# LinearSensor_inputs.net
KiCad netlist of a schematic drawn in Altium Designer
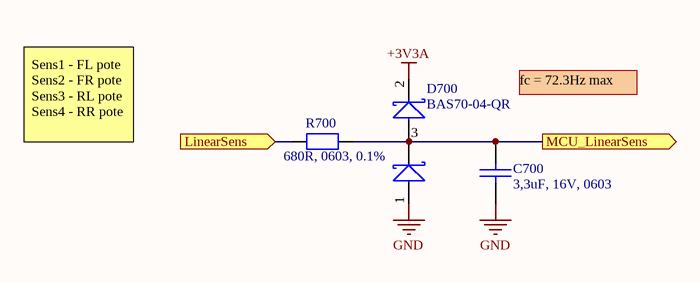
[diagram p0: LinearSensor_inputs.SchDoc]

(export (version "E")
  (design (tool "Eeschema 10.0.6"))
  (components
    (comp (ref "C700")
      (value "3,3uF, 16V, 0603")
      (footprint "CAP [0603] 1608")
      (description "Default capacitor part")
      (libsource (lib "Formula Student Team Tallinn (Estonia)") (part "Capacitor"))
    )
    (comp (ref "D700")
      (value "BAS70-04-QR")
      (footprint "SOT23-3")
      (description "Diode Small Signal Schottky 70V 70mA 3-Pin SOT-23 T/R")
      (fields (field (name "MANUFACTURER") "Nexperia"))
      (libsource (lib "Formula Student Team Tallinn (Estonia)") (part "Diode Rail-to-rail"))
    )
    (comp (ref "R700")
      (value "680R, 0603, 0.1%")
      (footprint "RES [0603] 1608")
      (description "Standard resistor part")
      (libsource (lib "Formula Student Team Tallinn (Estonia)") (part "Resistor"))
    )
  )
  (nets
    (net (code "1") (name "+3V3A") (class "Default")
      (node (ref "D700") (pin "2") (pinfunction "2_2") (pintype "passive"))
    )
    (net (code "2") (name "/LinearSens") (class "Default")
      (node (ref "R700") (pin "2") (pinfunction "2_2") (pintype "passive"))
    )
    (net (code "3") (name "/MCU_LinearSens") (class "Default")
      (node (ref "C700") (pin "1") (pinfunction "1_1") (pintype "passive"))
      (node (ref "D700") (pin "3") (pinfunction "3_3") (pintype "passive"))
      (node (ref "R700") (pin "1") (pinfunction "1_1") (pintype "passive"))
    )
    (net (code "4") (name "GND") (class "Default")
      (node (ref "C700") (pin "2") (pinfunction "2_2") (pintype "passive"))
      (node (ref "D700") (pin "1") (pinfunction "1_1") (pintype "passive"))
    )
  )
)
